# AnalogFrontend.net
KiCad netlist of a schematic drawn in Altium Designer
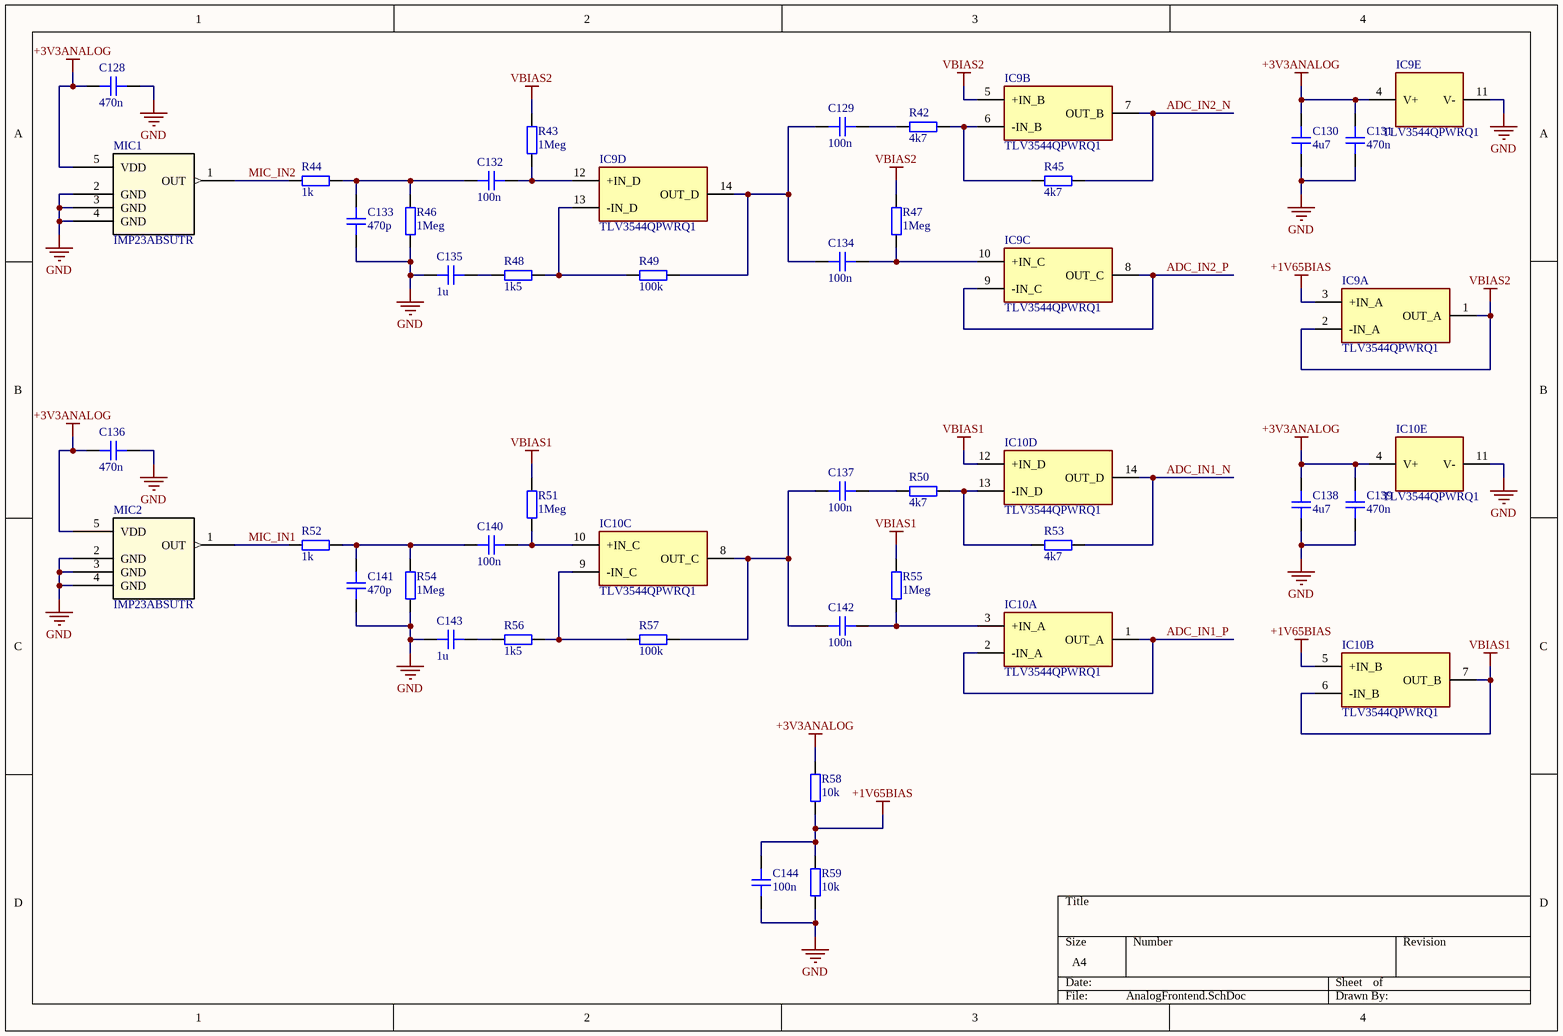
[diagram p0: AnalogFrontend.SchDoc]

(export (version "E")
  (design (tool "Eeschema 10.0.6"))
  (components
    (comp (ref "C128")
      (value "470n")
      (footprint "CAP_0201")
      (description "Capacitor SMD 0201")
      (libsource (lib "Schematic-Lib-PhilsLab") (part "CAP_0201"))
    )
    (comp (ref "C129")
      (value "100n")
      (footprint "CAP_0402")
      (description "Capacitor SMD 0402")
      (libsource (lib "Schematic-Lib-PhilsLab") (part "CAP_0402"))
    )
    (comp (ref "C130")
      (value "4u7")
      (footprint "CAP_0402")
      (description "Capacitor SMD 0402")
      (libsource (lib "Schematic-Lib-PhilsLab") (part "CAP_0402"))
    )
    (comp (ref "C131")
      (value "470n")
      (footprint "CAP_0201")
      (description "Capacitor SMD 0201")
      (libsource (lib "Schematic-Lib-PhilsLab") (part "CAP_0201"))
    )
    (comp (ref "C132")
      (value "100n")
      (footprint "CAP_0402")
      (description "Capacitor SMD 0402")
      (libsource (lib "Schematic-Lib-PhilsLab") (part "CAP_0402"))
    )
    (comp (ref "C133")
      (value "470p")
      (footprint "CAP_0402")
      (description "Capacitor SMD 0402")
      (libsource (lib "Schematic-Lib-PhilsLab") (part "CAP_0402"))
    )
    (comp (ref "C134")
      (value "100n")
      (footprint "CAP_0402")
      (description "Capacitor SMD 0402")
      (libsource (lib "Schematic-Lib-PhilsLab") (part "CAP_0402"))
    )
    (comp (ref "C135")
      (value "1u")
      (footprint "CAP_0402")
      (description "Capacitor SMD 0402")
      (libsource (lib "Schematic-Lib-PhilsLab") (part "CAP_0402"))
    )
    (comp (ref "C136")
      (value "470n")
      (footprint "CAP_0201")
      (description "Capacitor SMD 0201")
      (libsource (lib "Schematic-Lib-PhilsLab") (part "CAP_0201"))
    )
    (comp (ref "C137")
      (value "100n")
      (footprint "CAP_0402")
      (description "Capacitor SMD 0402")
      (libsource (lib "Schematic-Lib-PhilsLab") (part "CAP_0402"))
    )
    (comp (ref "C138")
      (value "4u7")
      (footprint "CAP_0402")
      (description "Capacitor SMD 0402")
      (libsource (lib "Schematic-Lib-PhilsLab") (part "CAP_0402"))
    )
    (comp (ref "C139")
      (value "470n")
      (footprint "CAP_0201")
      (description "Capacitor SMD 0201")
      (libsource (lib "Schematic-Lib-PhilsLab") (part "CAP_0201"))
    )
    (comp (ref "C140")
      (value "100n")
      (footprint "CAP_0402")
      (description "Capacitor SMD 0402")
      (libsource (lib "Schematic-Lib-PhilsLab") (part "CAP_0402"))
    )
    (comp (ref "C141")
      (value "470p")
      (footprint "CAP_0402")
      (description "Capacitor SMD 0402")
      (libsource (lib "Schematic-Lib-PhilsLab") (part "CAP_0402"))
    )
    (comp (ref "C142")
      (value "100n")
      (footprint "CAP_0402")
      (description "Capacitor SMD 0402")
      (libsource (lib "Schematic-Lib-PhilsLab") (part "CAP_0402"))
    )
    (comp (ref "C143")
      (value "1u")
      (footprint "CAP_0402")
      (description "Capacitor SMD 0402")
      (libsource (lib "Schematic-Lib-PhilsLab") (part "CAP_0402"))
    )
    (comp (ref "C144")
      (value "100n")
      (footprint "CAP_0402")
      (description "Capacitor SMD 0402")
      (libsource (lib "Schematic-Lib-PhilsLab") (part "CAP_0402"))
    )
    (comp (ref "IC9")
      (value "TLV3544QPWRQ1")
      (footprint "Footprint-Lib-PhilsLab:SOP65P640X120-14N")
      (description "Integrated Circuit")
      (fields (field (name "MOUSER PART NUMBER") "595-TLV3544QPWRQ1"))
      (libsource (lib "Schematic-Lib-PhilsLab") (part "TLV3544QPWRQ1"))
    )
    (comp (ref "IC10")
      (value "TLV3544QPWRQ1")
      (footprint "Footprint-Lib-PhilsLab:SOP65P640X120-14N")
      (description "Integrated Circuit")
      (fields (field (name "MOUSER PART NUMBER") "595-TLV3544QPWRQ1"))
      (libsource (lib "Schematic-Lib-PhilsLab") (part "TLV3544QPWRQ1"))
    )
    (comp (ref "MIC1")
      (value "IMP23ABSUTR")
      (footprint "RHLGA5_3P5X2P65X0P98_STM")
      (description "No Description Available")
      (libsource (lib "Schematic-Lib-PhilsLab") (part "IMP23ABSUTR"))
    )
    (comp (ref "MIC2")
      (value "IMP23ABSUTR")
      (footprint "RHLGA5_3P5X2P65X0P98_STM")
      (description "No Description Available")
      (libsource (lib "Schematic-Lib-PhilsLab") (part "IMP23ABSUTR"))
    )
    (comp (ref "R42")
      (value "4k7")
      (footprint "RES_0402")
      (description "Resistor SMD 0402")
      (libsource (lib "Schematic-Lib-PhilsLab") (part "RES_0402"))
    )
    (comp (ref "R43")
      (value "1Meg")
      (footprint "RES_0402")
      (description "Resistor SMD 0402")
      (libsource (lib "Schematic-Lib-PhilsLab") (part "RES_0402"))
    )
    (comp (ref "R44")
      (value "1k")
      (footprint "RES_0402")
      (description "Resistor SMD 0402")
      (libsource (lib "Schematic-Lib-PhilsLab") (part "RES_0402"))
    )
    (comp (ref "R45")
      (value "4k7")
      (footprint "RES_0402")
      (description "Resistor SMD 0402")
      (libsource (lib "Schematic-Lib-PhilsLab") (part "RES_0402"))
    )
    (comp (ref "R46")
      (value "1Meg")
      (footprint "RES_0402")
      (description "Resistor SMD 0402")
      (libsource (lib "Schematic-Lib-PhilsLab") (part "RES_0402"))
    )
    (comp (ref "R47")
      (value "1Meg")
      (footprint "RES_0402")
      (description "Resistor SMD 0402")
      (libsource (lib "Schematic-Lib-PhilsLab") (part "RES_0402"))
    )
    (comp (ref "R48")
      (value "1k5")
      (footprint "RES_0402")
      (description "Resistor SMD 0402")
      (libsource (lib "Schematic-Lib-PhilsLab") (part "RES_0402"))
    )
    (comp (ref "R49")
      (value "100k")
      (footprint "RES_0402")
      (description "Resistor SMD 0402")
      (libsource (lib "Schematic-Lib-PhilsLab") (part "RES_0402"))
    )
    (comp (ref "R50")
      (value "4k7")
      (footprint "RES_0402")
      (description "Resistor SMD 0402")
      (libsource (lib "Schematic-Lib-PhilsLab") (part "RES_0402"))
    )
    (comp (ref "R51")
      (value "1Meg")
      (footprint "RES_0402")
      (description "Resistor SMD 0402")
      (libsource (lib "Schematic-Lib-PhilsLab") (part "RES_0402"))
    )
    (comp (ref "R52")
      (value "1k")
      (footprint "RES_0402")
      (description "Resistor SMD 0402")
      (libsource (lib "Schematic-Lib-PhilsLab") (part "RES_0402"))
    )
    (comp (ref "R53")
      (value "4k7")
      (footprint "RES_0402")
      (description "Resistor SMD 0402")
      (libsource (lib "Schematic-Lib-PhilsLab") (part "RES_0402"))
    )
    (comp (ref "R54")
      (value "1Meg")
      (footprint "RES_0402")
      (description "Resistor SMD 0402")
      (libsource (lib "Schematic-Lib-PhilsLab") (part "RES_0402"))
    )
    (comp (ref "R55")
      (value "1Meg")
      (footprint "RES_0402")
      (description "Resistor SMD 0402")
      (libsource (lib "Schematic-Lib-PhilsLab") (part "RES_0402"))
    )
    (comp (ref "R56")
      (value "1k5")
      (footprint "RES_0402")
      (description "Resistor SMD 0402")
      (libsource (lib "Schematic-Lib-PhilsLab") (part "RES_0402"))
    )
    (comp (ref "R57")
      (value "100k")
      (footprint "RES_0402")
      (description "Resistor SMD 0402")
      (libsource (lib "Schematic-Lib-PhilsLab") (part "RES_0402"))
    )
    (comp (ref "R58")
      (value "10k")
      (footprint "RES_0402")
      (description "Resistor SMD 0402")
      (libsource (lib "Schematic-Lib-PhilsLab") (part "RES_0402"))
    )
    (comp (ref "R59")
      (value "10k")
      (footprint "RES_0402")
      (description "Resistor SMD 0402")
      (libsource (lib "Schematic-Lib-PhilsLab") (part "RES_0402"))
    )
  )
  (nets
    (net (code "1") (name "+1V65BIAS") (class "Default")
      (node (ref "C144") (pin "1") (pinfunction "1_1") (pintype "passive"))
      (node (ref "IC10") (pin "5") (pinfunction "+IN_B_5") (pintype "passive"))
      (node (ref "IC9") (pin "3") (pinfunction "+IN_A_3") (pintype "passive"))
      (node (ref "R58") (pin "1") (pinfunction "1_1") (pintype "passive"))
      (node (ref "R59") (pin "2") (pinfunction "2_2") (pintype "passive"))
    )
    (net (code "2") (name "+3V3ANALOG") (class "Default")
      (node (ref "C128") (pin "2") (pinfunction "2_2") (pintype "passive"))
      (node (ref "C130") (pin "2") (pinfunction "2_2") (pintype "passive"))
      (node (ref "C131") (pin "2") (pinfunction "2_2") (pintype "passive"))
      (node (ref "C136") (pin "2") (pinfunction "2_2") (pintype "passive"))
      (node (ref "C138") (pin "2") (pinfunction "2_2") (pintype "passive"))
      (node (ref "C139") (pin "2") (pinfunction "2_2") (pintype "passive"))
      (node (ref "IC10") (pin "4") (pinfunction "V+_4") (pintype "passive"))
      (node (ref "IC9") (pin "4") (pinfunction "V+_4") (pintype "passive"))
      (node (ref "MIC1") (pin "5") (pinfunction "VDD_5") (pintype "power_in"))
      (node (ref "MIC2") (pin "5") (pinfunction "VDD_5") (pintype "power_in"))
      (node (ref "R58") (pin "2") (pinfunction "2_2") (pintype "passive"))
    )
    (net (code "3") (name "/ADC_IN1_N") (class "Default")
      (node (ref "IC10") (pin "14") (pinfunction "OUT_D_14") (pintype "passive"))
      (node (ref "R53") (pin "2") (pinfunction "2_2") (pintype "passive"))
    )
    (net (code "4") (name "/ADC_IN1_P") (class "Default")
      (node (ref "IC10") (pin "1") (pinfunction "OUT_A_1") (pintype "passive"))
      (node (ref "IC10") (pin "2") (pinfunction "-IN_A_2") (pintype "passive"))
    )
    (net (code "5") (name "/ADC_IN2_N") (class "Default")
      (node (ref "IC9") (pin "7") (pinfunction "OUT_B_7") (pintype "passive"))
      (node (ref "R45") (pin "2") (pinfunction "2_2") (pintype "passive"))
    )
    (net (code "6") (name "/ADC_IN2_P") (class "Default")
      (node (ref "IC9") (pin "8") (pinfunction "OUT_C_8") (pintype "passive"))
      (node (ref "IC9") (pin "9") (pinfunction "-IN_C_9") (pintype "passive"))
    )
    (net (code "7") (name "/MIC_IN1") (class "Default")
      (node (ref "MIC2") (pin "1") (pinfunction "OUT_1") (pintype "output"))
      (node (ref "R52") (pin "2") (pinfunction "2_2") (pintype "passive"))
    )
    (net (code "8") (name "/MIC_IN2") (class "Default")
      (node (ref "MIC1") (pin "1") (pinfunction "OUT_1") (pintype "output"))
      (node (ref "R44") (pin "2") (pinfunction "2_2") (pintype "passive"))
    )
    (net (code "9") (name "GND") (class "Default")
      (node (ref "C128") (pin "1") (pinfunction "1_1") (pintype "passive"))
      (node (ref "C130") (pin "1") (pinfunction "1_1") (pintype "passive"))
      (node (ref "C131") (pin "1") (pinfunction "1_1") (pintype "passive"))
      (node (ref "C133") (pin "2") (pinfunction "2_2") (pintype "passive"))
      (node (ref "C135") (pin "1") (pinfunction "1_1") (pintype "passive"))
      (node (ref "C136") (pin "1") (pinfunction "1_1") (pintype "passive"))
      (node (ref "C138") (pin "1") (pinfunction "1_1") (pintype "passive"))
      (node (ref "C139") (pin "1") (pinfunction "1_1") (pintype "passive"))
      (node (ref "C141") (pin "2") (pinfunction "2_2") (pintype "passive"))
      (node (ref "C143") (pin "1") (pinfunction "1_1") (pintype "passive"))
      (node (ref "C144") (pin "2") (pinfunction "2_2") (pintype "passive"))
      (node (ref "IC10") (pin "11") (pinfunction "V-_11") (pintype "passive"))
      (node (ref "IC9") (pin "11") (pinfunction "V-_11") (pintype "passive"))
      (node (ref "MIC1") (pin "2") (pinfunction "GND_2") (pintype "power_in"))
      (node (ref "MIC1") (pin "3") (pinfunction "GND_3") (pintype "power_in"))
      (node (ref "MIC1") (pin "4") (pinfunction "GND_4") (pintype "power_in"))
      (node (ref "MIC2") (pin "2") (pinfunction "GND_2") (pintype "power_in"))
      (node (ref "MIC2") (pin "3") (pinfunction "GND_3") (pintype "power_in"))
      (node (ref "MIC2") (pin "4") (pinfunction "GND_4") (pintype "power_in"))
      (node (ref "R46") (pin "1") (pinfunction "1_1") (pintype "passive"))
      (node (ref "R54") (pin "1") (pinfunction "1_1") (pintype "passive"))
      (node (ref "R59") (pin "1") (pinfunction "1_1") (pintype "passive"))
    )
    (net (code "10") (name "Net-(C129-Pad1)") (class "Default")
      (node (ref "C129") (pin "1") (pinfunction "1_1") (pintype "passive"))
      (node (ref "R42") (pin "1") (pinfunction "1_1") (pintype "passive"))
    )
    (net (code "11") (name "Net-(C132-Pad2)") (class "Default")
      (node (ref "C132") (pin "2") (pinfunction "2_2") (pintype "passive"))
      (node (ref "C133") (pin "1") (pinfunction "1_1") (pintype "passive"))
      (node (ref "R44") (pin "1") (pinfunction "1_1") (pintype "passive"))
      (node (ref "R46") (pin "2") (pinfunction "2_2") (pintype "passive"))
    )
    (net (code "12") (name "Net-(C135-Pad2)") (class "Default")
      (node (ref "C135") (pin "2") (pinfunction "2_2") (pintype "passive"))
      (node (ref "R48") (pin "1") (pinfunction "1_1") (pintype "passive"))
    )
    (net (code "13") (name "Net-(C137-Pad1)") (class "Default")
      (node (ref "C137") (pin "1") (pinfunction "1_1") (pintype "passive"))
      (node (ref "R50") (pin "1") (pinfunction "1_1") (pintype "passive"))
    )
    (net (code "14") (name "Net-(C140-Pad2)") (class "Default")
      (node (ref "C140") (pin "2") (pinfunction "2_2") (pintype "passive"))
      (node (ref "C141") (pin "1") (pinfunction "1_1") (pintype "passive"))
      (node (ref "R52") (pin "1") (pinfunction "1_1") (pintype "passive"))
      (node (ref "R54") (pin "2") (pinfunction "2_2") (pintype "passive"))
    )
    (net (code "15") (name "Net-(C143-Pad2)") (class "Default")
      (node (ref "C143") (pin "2") (pinfunction "2_2") (pintype "passive"))
      (node (ref "R56") (pin "1") (pinfunction "1_1") (pintype "passive"))
    )
    (net (code "16") (name "Net-(IC9B--IN_B)") (class "Default")
      (node (ref "IC9") (pin "6") (pinfunction "-IN_B_6") (pintype "passive"))
      (node (ref "R42") (pin "2") (pinfunction "2_2") (pintype "passive"))
      (node (ref "R45") (pin "1") (pinfunction "1_1") (pintype "passive"))
    )
    (net (code "17") (name "Net-(IC9C-+IN_C)") (class "Default")
      (node (ref "C134") (pin "1") (pinfunction "1_1") (pintype "passive"))
      (node (ref "IC9") (pin "10") (pinfunction "+IN_C_10") (pintype "passive"))
      (node (ref "R47") (pin "1") (pinfunction "1_1") (pintype "passive"))
    )
    (net (code "18") (name "Net-(IC9D-+IN_D)") (class "Default")
      (node (ref "C132") (pin "1") (pinfunction "1_1") (pintype "passive"))
      (node (ref "IC9") (pin "12") (pinfunction "+IN_D_12") (pintype "passive"))
      (node (ref "R43") (pin "1") (pinfunction "1_1") (pintype "passive"))
    )
    (net (code "19") (name "Net-(IC9D--IN_D)") (class "Default")
      (node (ref "IC9") (pin "13") (pinfunction "-IN_D_13") (pintype "passive"))
      (node (ref "R48") (pin "2") (pinfunction "2_2") (pintype "passive"))
      (node (ref "R49") (pin "1") (pinfunction "1_1") (pintype "passive"))
    )
    (net (code "20") (name "Net-(IC9D-OUT_D)") (class "Default")
      (node (ref "C129") (pin "2") (pinfunction "2_2") (pintype "passive"))
      (node (ref "C134") (pin "2") (pinfunction "2_2") (pintype "passive"))
      (node (ref "IC9") (pin "14") (pinfunction "OUT_D_14") (pintype "passive"))
      (node (ref "R49") (pin "2") (pinfunction "2_2") (pintype "passive"))
    )
    (net (code "21") (name "Net-(IC10A-+IN_A)") (class "Default")
      (node (ref "C142") (pin "1") (pinfunction "1_1") (pintype "passive"))
      (node (ref "IC10") (pin "3") (pinfunction "+IN_A_3") (pintype "passive"))
      (node (ref "R55") (pin "1") (pinfunction "1_1") (pintype "passive"))
    )
    (net (code "22") (name "Net-(IC10C-+IN_C)") (class "Default")
      (node (ref "C140") (pin "1") (pinfunction "1_1") (pintype "passive"))
      (node (ref "IC10") (pin "10") (pinfunction "+IN_C_10") (pintype "passive"))
      (node (ref "R51") (pin "1") (pinfunction "1_1") (pintype "passive"))
    )
    (net (code "23") (name "Net-(IC10C--IN_C)") (class "Default")
      (node (ref "IC10") (pin "9") (pinfunction "-IN_C_9") (pintype "passive"))
      (node (ref "R56") (pin "2") (pinfunction "2_2") (pintype "passive"))
      (node (ref "R57") (pin "1") (pinfunction "1_1") (pintype "passive"))
    )
    (net (code "24") (name "Net-(IC10C-OUT_C)") (class "Default")
      (node (ref "C137") (pin "2") (pinfunction "2_2") (pintype "passive"))
      (node (ref "C142") (pin "2") (pinfunction "2_2") (pintype "passive"))
      (node (ref "IC10") (pin "8") (pinfunction "OUT_C_8") (pintype "passive"))
      (node (ref "R57") (pin "2") (pinfunction "2_2") (pintype "passive"))
    )
    (net (code "25") (name "Net-(IC10D--IN_D)") (class "Default")
      (node (ref "IC10") (pin "13") (pinfunction "-IN_D_13") (pintype "passive"))
      (node (ref "R50") (pin "2") (pinfunction "2_2") (pintype "passive"))
      (node (ref "R53") (pin "1") (pinfunction "1_1") (pintype "passive"))
    )
    (net (code "26") (name "VBIAS1") (class "Default")
      (node (ref "IC10") (pin "12") (pinfunction "+IN_D_12") (pintype "passive"))
      (node (ref "IC10") (pin "6") (pinfunction "-IN_B_6") (pintype "passive"))
      (node (ref "IC10") (pin "7") (pinfunction "OUT_B_7") (pintype "passive"))
      (node (ref "R51") (pin "2") (pinfunction "2_2") (pintype "passive"))
      (node (ref "R55") (pin "2") (pinfunction "2_2") (pintype "passive"))
    )
    (net (code "27") (name "VBIAS2") (class "Default")
      (node (ref "IC9") (pin "1") (pinfunction "OUT_A_1") (pintype "passive"))
      (node (ref "IC9") (pin "2") (pinfunction "-IN_A_2") (pintype "passive"))
      (node (ref "IC9") (pin "5") (pinfunction "+IN_B_5") (pintype "passive"))
      (node (ref "R43") (pin "2") (pinfunction "2_2") (pintype "passive"))
      (node (ref "R47") (pin "2") (pinfunction "2_2") (pintype "passive"))
    )
  )
)
